# RAK3172.net
KiCad netlist of a schematic drawn in Altium Designer
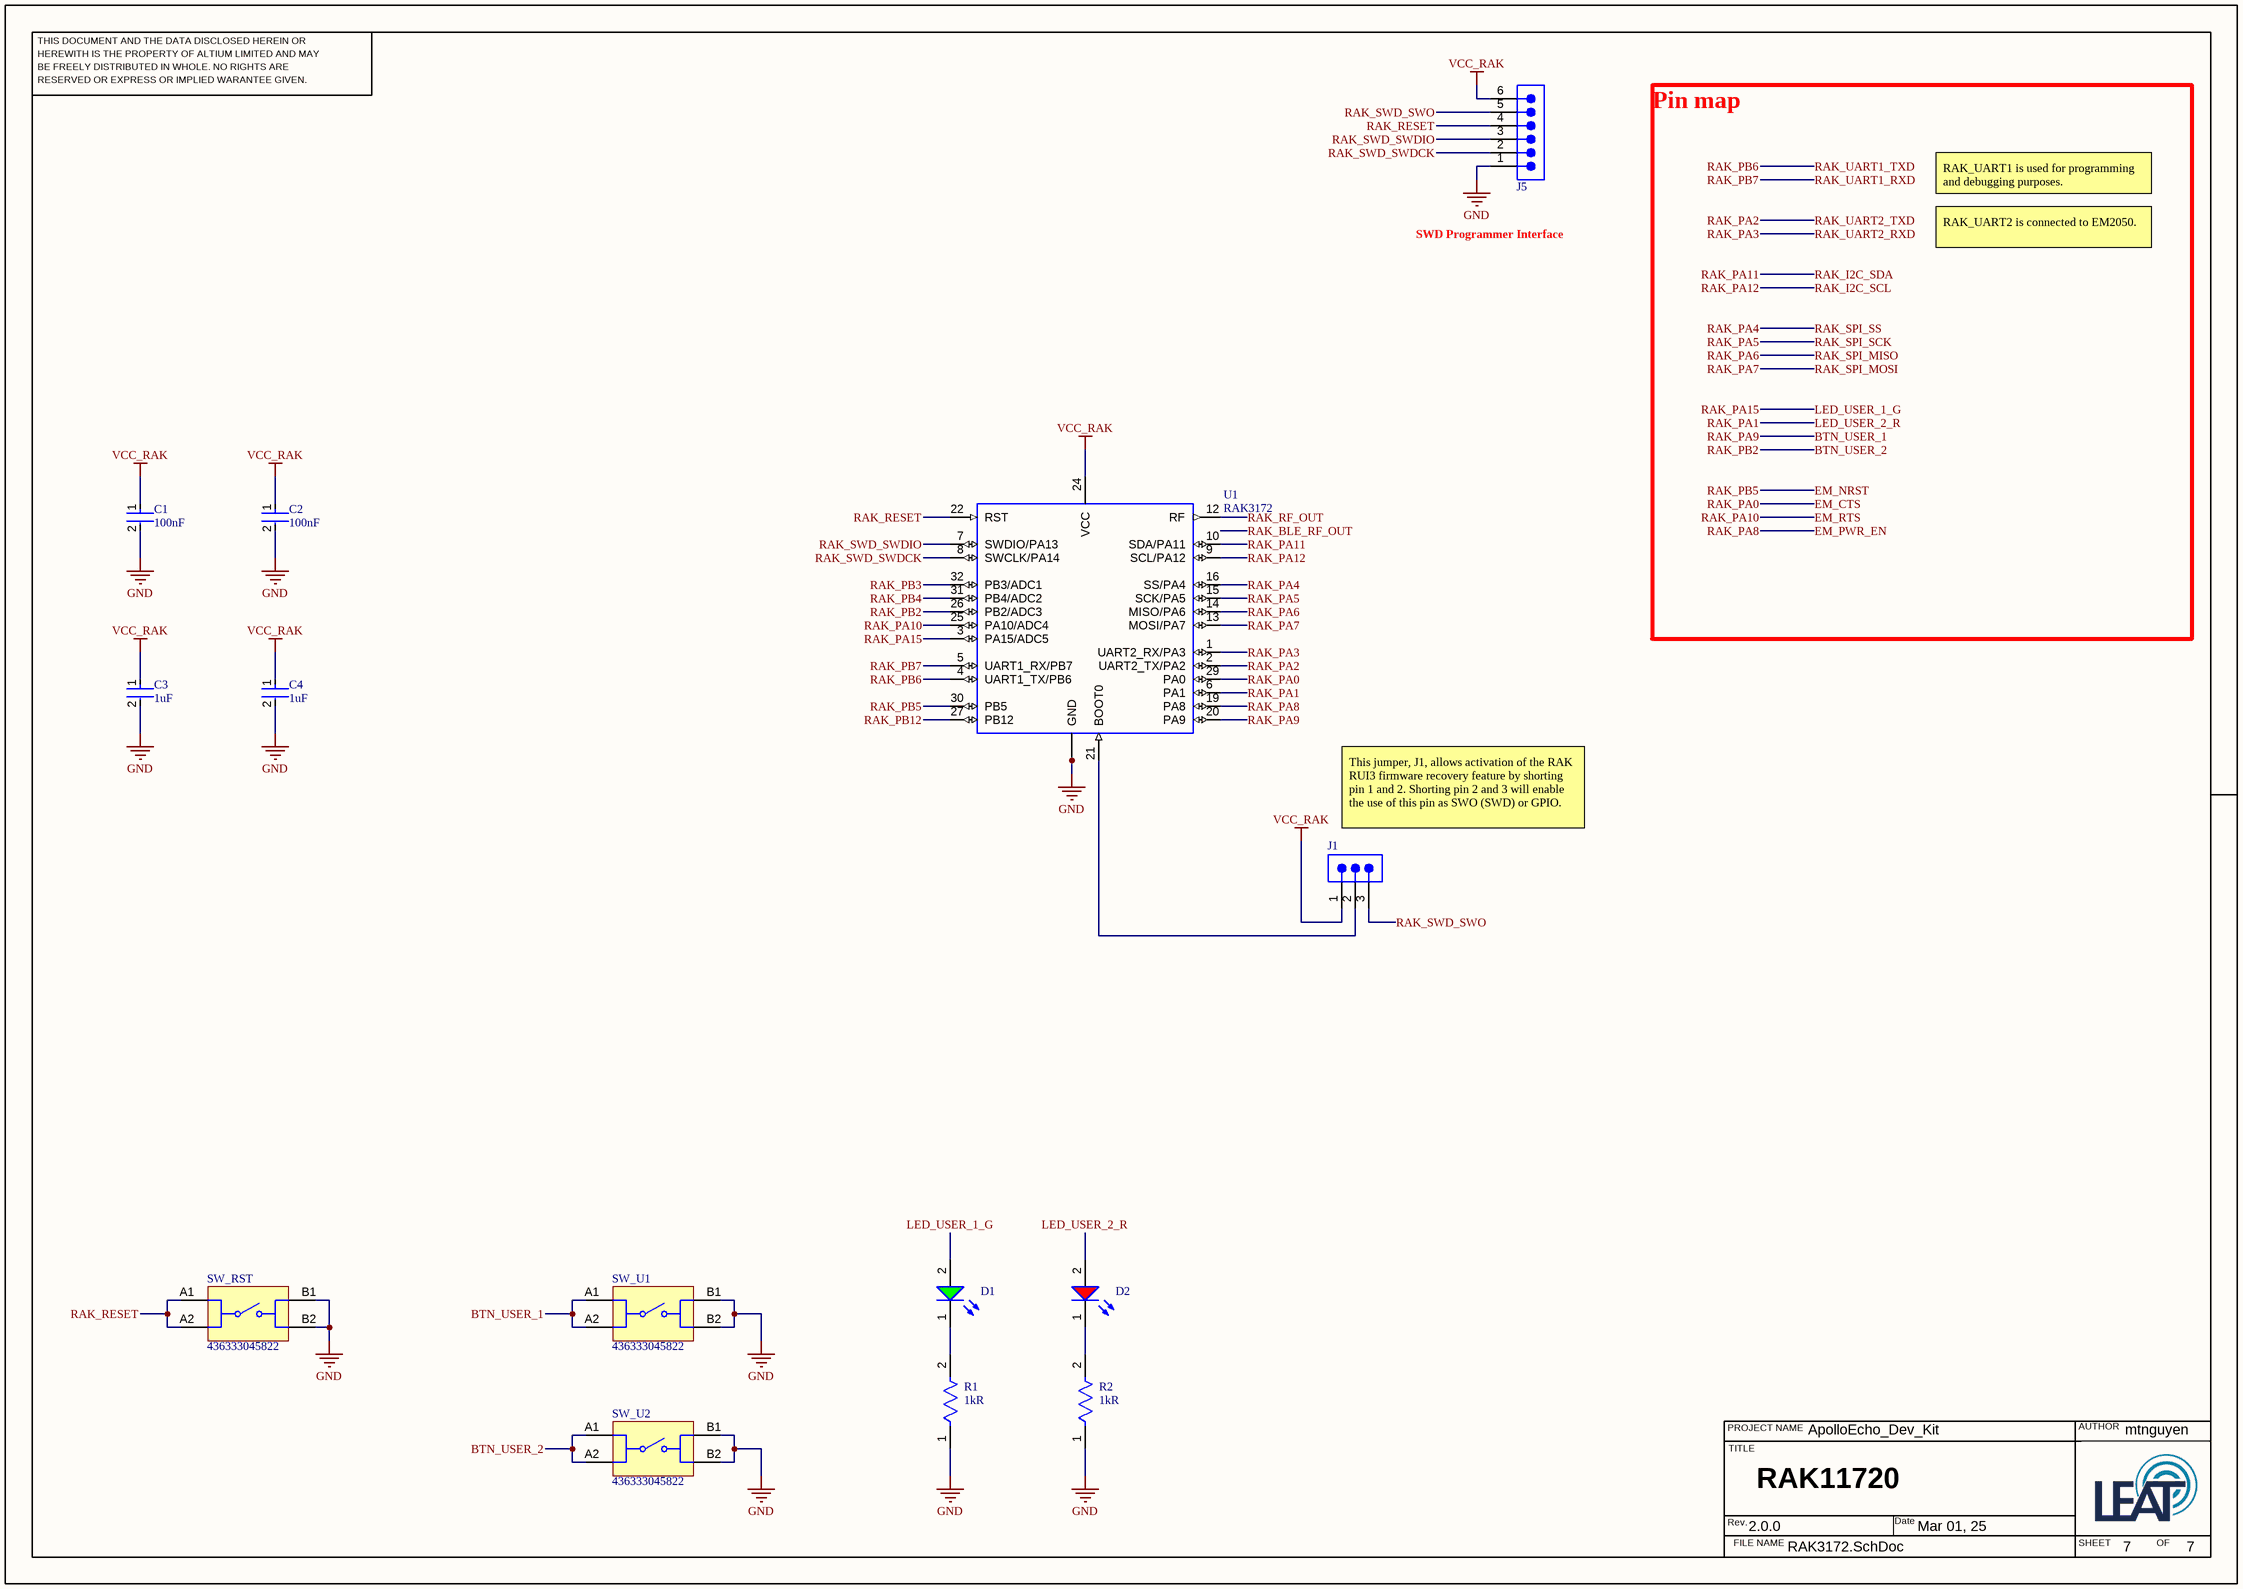
[diagram p0: RAK3172.SchDoc]

(export (version "E")
  (design (tool "Eeschema 10.0.6"))
  (components
    (comp (ref "C1")
      (value "0402ZD104KAT2A")
      (footprint "FP-0402-L_1_0_1-W_0_5_0_1-IPC_C")
      (description "General Purpose Ceramic Capacitor, 0402, 100nF, 10%, X5R, 15%, 10V")
      (fields
        (field (name "VOLTAGE") "10V")
        (field (name "TOLERANCE") "10%")
        (field (name "CAPACITANCE") "100nF")
      )
      (libsource (lib "Altium Content Vault") (part "b4654b650e69147ec39a6b967a45e02"))
    )
    (comp (ref "C2")
      (value "0402ZD104KAT2A")
      (footprint "FP-0402-L_1_0_1-W_0_5_0_1-IPC_C")
      (description "General Purpose Ceramic Capacitor, 0402, 100nF, 10%, X5R, 15%, 10V")
      (fields
        (field (name "VOLTAGE") "10V")
        (field (name "TOLERANCE") "10%")
        (field (name "CAPACITANCE") "100nF")
      )
      (libsource (lib "Altium Content Vault") (part "b4654b650e69147ec39a6b967a45e02"))
    )
    (comp (ref "C3")
      (value "EMK105BJ105KV-F")
      (footprint "FP-0402-L_1_0_0_05-W_0_5-IPC_A")
      (description "None")
      (fields (field (name "TOLERANCE") "10%") (field (name "CAPACITANCE") "1uF"))
      (libsource (lib "Altium Content Vault") (part "b4654b650e69147ec39a6b967a45e02"))
    )
    (comp (ref "C4")
      (value "EMK105BJ105KV-F")
      (footprint "FP-0402-L_1_0_0_05-W_0_5-IPC_A")
      (description "None")
      (fields (field (name "TOLERANCE") "10%") (field (name "CAPACITANCE") "1uF"))
      (libsource (lib "Altium Content Vault") (part "b4654b650e69147ec39a6b967a45e02"))
    )
    (comp (ref "D1")
      (value "150060VS75000")
      (footprint "WL-SMCW_0603_150060xx75000")
      (description "WURTH ELEKTRONIK - 150060VS75000 - LED, Green, SMD, 0603, 30 mA, 2 V, 570 nm")
      (libsource (lib "Altium Content Vault") (part "LED_Green_2A-1K"))
    )
    (comp (ref "D2")
      (value "150060RS75000")
      (footprint "WL-SMCW_0603_150060xx75000")
      (description "LED Low-Power Uni-Color Red 630nm 2V 2-Pin Chip 0603(1608Metric) T/R")
      (libsource (lib "Altium Content Vault") (part "LED_Red_2A-1K"))
    )
    (comp (ref "J1")
      (value "61300311121")
      (footprint "61300311121")
      (libsource (lib "Altium Content Vault") (part "Header_Male_1R_03P"))
    )
    (comp (ref "J5")
      (value "61300611121")
      (footprint "61300611121")
      (libsource (lib "Altium Content Vault") (part "Header_Male_1R_06P"))
    )
    (comp (ref "R1")
      (value "RMCF0402FT1K00")
      (footprint "FP-RMCF0402-IPC_A")
      (description "1kΩ ±1% 0.063W 0402 Thick Film Chip Resistor AEC-Q200 compliant")
      (fields (field (name "TOLERANCE") "1%") (field (name "RESISTANCE") "1kR"))
      (libsource (lib "Altium Content Vault") (part "1029c3af85768c4190bb7ad29bc67b5"))
    )
    (comp (ref "R2")
      (value "RMCF0402FT1K00")
      (footprint "FP-RMCF0402-IPC_A")
      (description "1kΩ ±1% 0.063W 0402 Thick Film Chip Resistor AEC-Q200 compliant")
      (fields (field (name "TOLERANCE") "1%") (field (name "RESISTANCE") "1kR"))
      (libsource (lib "Altium Content Vault") (part "1029c3af85768c4190bb7ad29bc67b5"))
    )
    (comp (ref "SW_RST")
      (value "436333045822")
      (footprint "436333045822")
      (libsource (lib "Altium Content Vault") (part "SPST-NO_4P"))
    )
    (comp (ref "SW_U1")
      (value "436333045822")
      (footprint "436333045822")
      (libsource (lib "Altium Content Vault") (part "SPST-NO_4P"))
    )
    (comp (ref "SW_U2")
      (value "436333045822")
      (footprint "436333045822")
      (libsource (lib "Altium Content Vault") (part "SPST-NO_4P"))
    )
    (comp (ref "U1")
      (value "RAK3172")
      (footprint "RAK3172")
      (fields (field (name "MF") "Shenzhen RAKwireless Technology Co.,Ltd."))
      (libsource (lib "RAK3172") (part "RAK3172"))
    )
  )
  (nets
    (net (code "1") (name "/BTN_USER_1") (class "Default")
      (node (ref "SW_U1") (pin "A1") (pinfunction "A1_A1") (pintype "passive"))
      (node (ref "SW_U1") (pin "A2") (pinfunction "A2_A2") (pintype "passive"))
      (node (ref "U1") (pin "20") (pinfunction "PA9_20") (pintype "bidirectional"))
    )
    (net (code "2") (name "/BTN_USER_2") (class "Default")
      (node (ref "SW_U2") (pin "A1") (pinfunction "A1_A1") (pintype "passive"))
      (node (ref "SW_U2") (pin "A2") (pinfunction "A2_A2") (pintype "passive"))
      (node (ref "U1") (pin "26") (pinfunction "PB2/ADC3_26") (pintype "bidirectional"))
    )
    (net (code "3") (name "/EM_CTS") (class "Default")
      (node (ref "U1") (pin "29") (pinfunction "PA0_29") (pintype "bidirectional"))
    )
    (net (code "4") (name "/EM_NRST") (class "Default")
      (node (ref "U1") (pin "30") (pinfunction "PB5_30") (pintype "bidirectional"))
    )
    (net (code "5") (name "/EM_PWR_EN") (class "Default")
      (node (ref "U1") (pin "19") (pinfunction "PA8_19") (pintype "bidirectional"))
    )
    (net (code "6") (name "/EM_RTS") (class "Default")
      (node (ref "U1") (pin "25") (pinfunction "PA10/ADC4_25") (pintype "bidirectional"))
    )
    (net (code "7") (name "/LED_USER_1_G") (class "Default")
      (node (ref "D1") (pin "2") (pinfunction "A_2") (pintype "passive"))
      (node (ref "U1") (pin "3") (pinfunction "PA15/ADC5_3") (pintype "bidirectional"))
    )
    (net (code "8") (name "/LED_USER_2_R") (class "Default")
      (node (ref "D2") (pin "2") (pinfunction "A_2") (pintype "passive"))
      (node (ref "U1") (pin "6") (pinfunction "PA1_6") (pintype "bidirectional"))
    )
    (net (code "10") (name "/RAK_I2C_SCL") (class "Default")
      (node (ref "U1") (pin "9") (pinfunction "SCL/PA12_9") (pintype "bidirectional"))
    )
    (net (code "11") (name "/RAK_I2C_SDA") (class "Default")
      (node (ref "U1") (pin "10") (pinfunction "SDA/PA11_10") (pintype "bidirectional"))
    )
    (net (code "12") (name "/RAK_PA2") (class "Default")
      (node (ref "U1") (pin "2") (pinfunction "UART2_TX/PA2_2") (pintype "bidirectional"))
    )
    (net (code "13") (name "/RAK_PA3") (class "Default")
      (node (ref "U1") (pin "1") (pinfunction "UART2_RX/PA3_1") (pintype "bidirectional"))
    )
    (net (code "14") (name "/RAK_PA4") (class "Default")
      (node (ref "U1") (pin "16") (pinfunction "SS/PA4_16") (pintype "bidirectional"))
    )
    (net (code "15") (name "/RAK_PA5") (class "Default")
      (node (ref "U1") (pin "15") (pinfunction "SCK/PA5_15") (pintype "bidirectional"))
    )
    (net (code "16") (name "/RAK_PA6") (class "Default")
      (node (ref "U1") (pin "14") (pinfunction "MISO/PA6_14") (pintype "bidirectional"))
    )
    (net (code "17") (name "/RAK_PA7") (class "Default")
      (node (ref "U1") (pin "13") (pinfunction "MOSI/PA7_13") (pintype "bidirectional"))
    )
    (net (code "18") (name "/RAK_PB3") (class "Default")
      (node (ref "U1") (pin "32") (pinfunction "PB3/ADC1_32") (pintype "bidirectional"))
    )
    (net (code "19") (name "/RAK_PB4") (class "Default")
      (node (ref "U1") (pin "31") (pinfunction "PB4/ADC2_31") (pintype "bidirectional"))
    )
    (net (code "20") (name "/RAK_PB6") (class "Default")
      (node (ref "U1") (pin "4") (pinfunction "UART1_TX/PB6_4") (pintype "bidirectional"))
    )
    (net (code "21") (name "/RAK_PB7") (class "Default")
      (node (ref "U1") (pin "5") (pinfunction "UART1_RX/PB7_5") (pintype "bidirectional"))
    )
    (net (code "22") (name "/RAK_PB12") (class "Default")
      (node (ref "U1") (pin "27") (pinfunction "PB12_27") (pintype "bidirectional"))
    )
    (net (code "23") (name "/RAK_RESET") (class "Default")
      (node (ref "J5") (pin "4") (pinfunction "4_4") (pintype "passive"))
      (node (ref "SW_RST") (pin "A1") (pinfunction "A1_A1") (pintype "passive"))
      (node (ref "SW_RST") (pin "A2") (pinfunction "A2_A2") (pintype "passive"))
      (node (ref "U1") (pin "22") (pinfunction "RST_22") (pintype "input"))
    )
    (net (code "24") (name "/RAK_RF_OUT") (class "Default")
      (node (ref "U1") (pin "12") (pinfunction "RF_12") (pintype "output"))
    )
    (net (code "25") (name "/RAK_SWD_SWDCK") (class "Default")
      (node (ref "J5") (pin "2") (pinfunction "2_2") (pintype "passive"))
      (node (ref "U1") (pin "8") (pinfunction "SWCLK/PA14_8") (pintype "bidirectional"))
    )
    (net (code "26") (name "/RAK_SWD_SWDIO") (class "Default")
      (node (ref "J5") (pin "3") (pinfunction "3_3") (pintype "passive"))
      (node (ref "U1") (pin "7") (pinfunction "SWDIO/PA13_7") (pintype "bidirectional"))
    )
    (net (code "27") (name "/RAK_SWD_SWO") (class "Default")
      (node (ref "J1") (pin "3") (pinfunction "3_3") (pintype "passive"))
      (node (ref "J5") (pin "5") (pinfunction "5_5") (pintype "passive"))
    )
    (net (code "28") (name "GND") (class "Default")
      (node (ref "C1") (pin "2") (pinfunction "2_2") (pintype "passive"))
      (node (ref "C2") (pin "2") (pinfunction "2_2") (pintype "passive"))
      (node (ref "C3") (pin "2") (pinfunction "2_2") (pintype "passive"))
      (node (ref "C4") (pin "2") (pinfunction "2_2") (pintype "passive"))
      (node (ref "J5") (pin "1") (pinfunction "1_1") (pintype "passive"))
      (node (ref "R1") (pin "1") (pinfunction "1_1") (pintype "passive"))
      (node (ref "R2") (pin "1") (pinfunction "1_1") (pintype "passive"))
      (node (ref "SW_RST") (pin "B1") (pinfunction "B1_B1") (pintype "passive"))
      (node (ref "SW_RST") (pin "B2") (pinfunction "B2_B2") (pintype "passive"))
      (node (ref "SW_U1") (pin "B1") (pinfunction "B1_B1") (pintype "passive"))
      (node (ref "SW_U1") (pin "B2") (pinfunction "B2_B2") (pintype "passive"))
      (node (ref "SW_U2") (pin "B1") (pinfunction "B1_B1") (pintype "passive"))
      (node (ref "SW_U2") (pin "B2") (pinfunction "B2_B2") (pintype "passive"))
      (node (ref "U1") (pin "11") (pinfunction "GND_11") (pintype "power_in"))
      (node (ref "U1") (pin "17") (pinfunction "GND_17") (pintype "power_in"))
      (node (ref "U1") (pin "18") (pinfunction "GND_18") (pintype "power_in"))
      (node (ref "U1") (pin "23") (pinfunction "GND_23") (pintype "power_in"))
      (node (ref "U1") (pin "28") (pinfunction "GND_28") (pintype "power_in"))
    )
    (net (code "29") (name "Net-(D1-K)") (class "Default")
      (node (ref "D1") (pin "1") (pinfunction "K_1") (pintype "passive"))
      (node (ref "R1") (pin "2") (pinfunction "2_2") (pintype "passive"))
    )
    (net (code "30") (name "Net-(D2-K)") (class "Default")
      (node (ref "D2") (pin "1") (pinfunction "K_1") (pintype "passive"))
      (node (ref "R2") (pin "2") (pinfunction "2_2") (pintype "passive"))
    )
    (net (code "31") (name "Net-(U1-BOOT0)") (class "Default")
      (node (ref "J1") (pin "2") (pinfunction "2_2") (pintype "passive"))
      (node (ref "U1") (pin "21") (pinfunction "BOOT0_21") (pintype "input"))
    )
    (net (code "32") (name "VCC_RAK") (class "Default")
      (node (ref "C1") (pin "1") (pinfunction "1_1") (pintype "passive"))
      (node (ref "C2") (pin "1") (pinfunction "1_1") (pintype "passive"))
      (node (ref "C3") (pin "1") (pinfunction "1_1") (pintype "passive"))
      (node (ref "C4") (pin "1") (pinfunction "1_1") (pintype "passive"))
      (node (ref "J1") (pin "1") (pinfunction "1_1") (pintype "passive"))
      (node (ref "J5") (pin "6") (pinfunction "6_6") (pintype "passive"))
      (node (ref "U1") (pin "24") (pinfunction "VCC_24") (pintype "power_in"))
    )
  )
)
